# Arducard.net
KiCad netlist of a schematic drawn in EAGLE
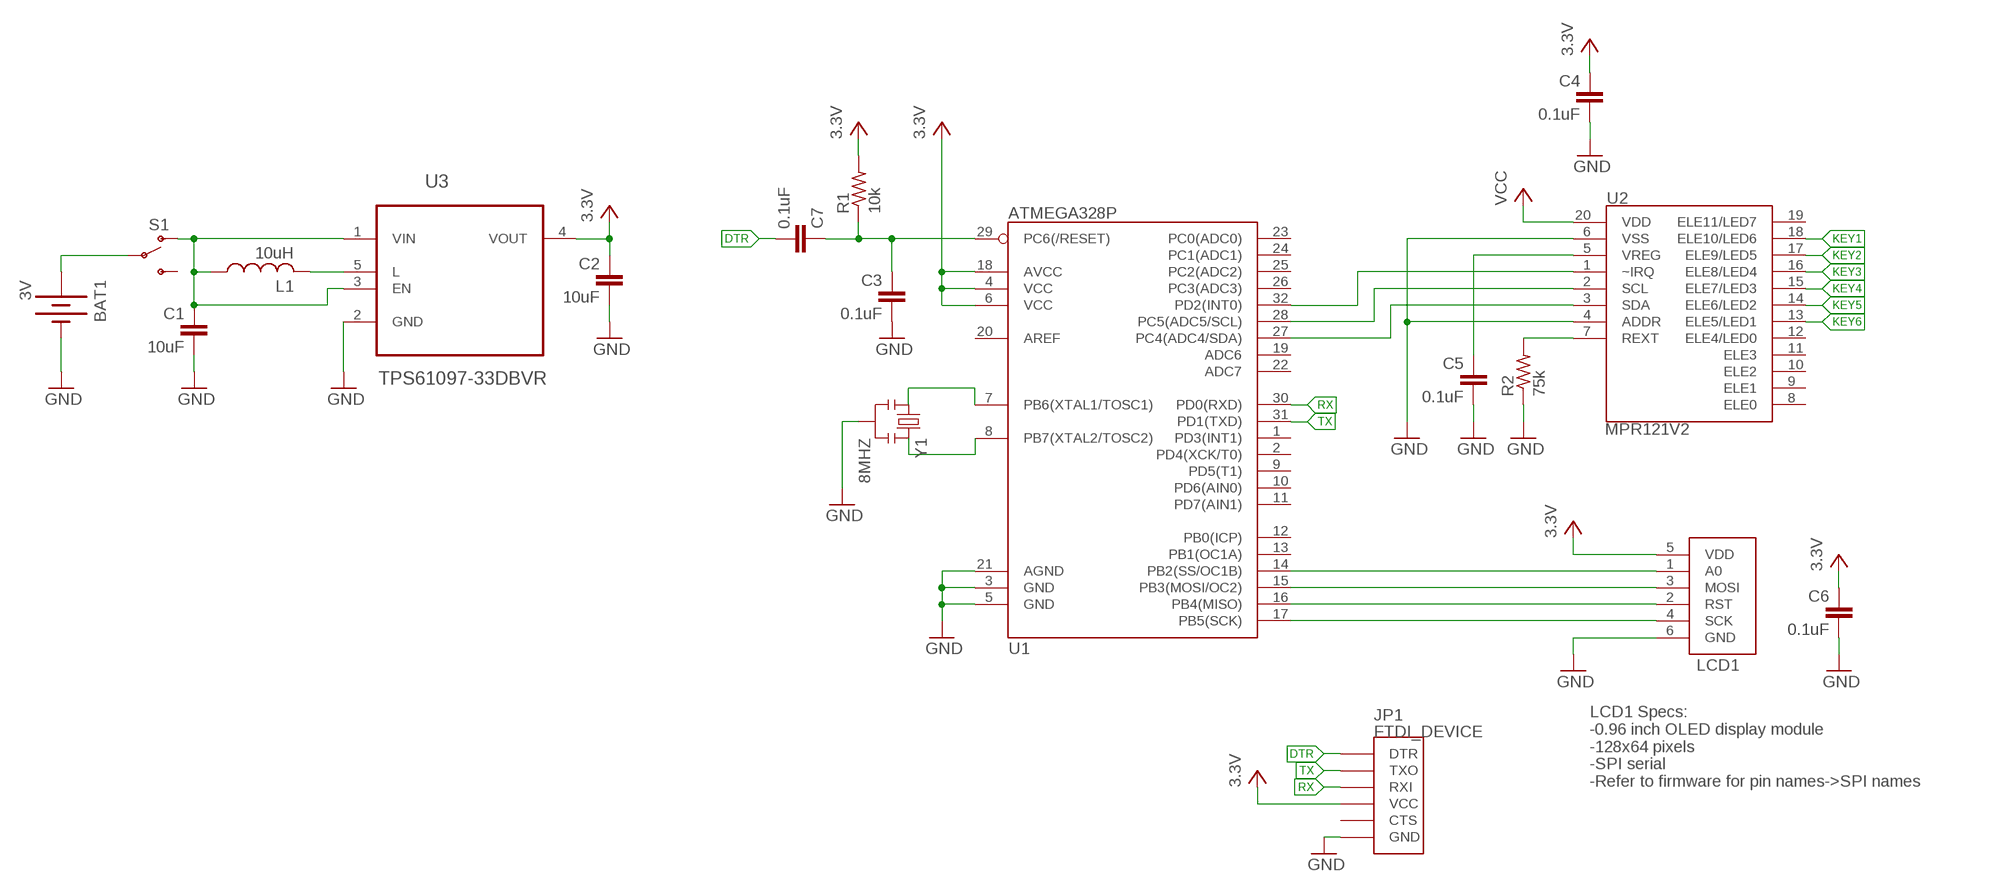
[diagram p0: schematic, sheet 1]

(export (version "E")
  (design (tool "Eeschema 10.0.6"))
  (components
    (comp (ref "BAT1")
      (value "3V")
      (footprint "eagle-import:BATTCON_20MM_4LEGS")
      (libsource (lib "eagle-import") (part "BATTERY20MM_4LEGS"))
    )
    (comp (ref "C1")
      (value "10uF")
      (footprint "eagle-import:C0603K")
      (libsource (lib "eagle-import") (part "C-EUC0603K"))
    )
    (comp (ref "C2")
      (value "10uF")
      (footprint "eagle-import:C0603K")
      (libsource (lib "eagle-import") (part "C-EUC0603K"))
    )
    (comp (ref "C3")
      (value "0.1uF")
      (footprint "eagle-import:C0603K")
      (libsource (lib "eagle-import") (part "C-EUC0603K"))
    )
    (comp (ref "C4")
      (value "0.1uF")
      (footprint "eagle-import:C0603K")
      (libsource (lib "eagle-import") (part "C-EUC0603K"))
    )
    (comp (ref "C5")
      (value "0.1uF")
      (footprint "eagle-import:C0603K")
      (libsource (lib "eagle-import") (part "C-EUC0603K"))
    )
    (comp (ref "C6")
      (value "0.1uF")
      (footprint "eagle-import:C0603K")
      (libsource (lib "eagle-import") (part "C-EUC0603K"))
    )
    (comp (ref "C7")
      (value "0.1uF")
      (footprint "eagle-import:C0603K")
      (libsource (lib "eagle-import") (part "C-EUC0603K"))
    )
    (comp (ref "JP1")
      (value "FTDI_DEVICE")
      (footprint "eagle-import:FTDI_DEVICE_SIDE")
      (libsource (lib "eagle-import") (part "FTDI_DEVICE"))
    )
    (comp (ref "L1")
      (value "10uH")
      (footprint "eagle-import:L2012C")
      (fields (field (name "MPN") "CKS21254R7M-T"))
      (libsource (lib "eagle-import") (part "L-USL2012C"))
    )
    (comp (ref "LCD1")
      (value "LCD")
      (footprint "eagle-import:LCD")
      (libsource (lib "eagle-import") (part "LCD"))
    )
    (comp (ref "R1")
      (value "10k")
      (footprint "eagle-import:R0603")
      (libsource (lib "eagle-import") (part "R-US_R0603"))
    )
    (comp (ref "R2")
      (value "75k")
      (footprint "eagle-import:R0603")
      (libsource (lib "eagle-import") (part "R-US_R0603"))
    )
    (comp (ref "S1")
      (value "SWITCH-SPDTSMD2")
      (footprint "eagle-import:SWITCH-SPDT-SMD")
      (libsource (lib "eagle-import") (part "SWITCH-SPDTSMD2"))
    )
    (comp (ref "U1")
      (value "ATMEGA328P")
      (footprint "eagle-import:TQFP32-08")
      (libsource (lib "eagle-import") (part "ATMEGA328_SMT"))
    )
    (comp (ref "U2")
      (value "MPR121V2")
      (footprint "eagle-import:QFN-20-0.4MM-V2")
      (libsource (lib "eagle-import") (part "MPR121V2"))
    )
    (comp (ref "U3")
      (value "TPS61097-33DBVR")
      (footprint "eagle-import:SOT95P280X145-5N")
      (libsource (lib "eagle-import") (part "TPS61097-33DBVR"))
    )
    (comp (ref "Y1")
      (value "8MHZ")
      (footprint "eagle-import:RESONATOR-SMD")
      (libsource (lib "eagle-import") (part "RESONATOR16MHZ"))
    )
  )
  (nets
    (net (code "1") (name "3.3V") (class "Default")
      (node (ref "C2") (pin "1") (pinfunction "1_1") (pintype "passive"))
      (node (ref "C4") (pin "1") (pinfunction "1_1") (pintype "passive"))
      (node (ref "C6") (pin "1") (pinfunction "1_1") (pintype "passive"))
      (node (ref "JP1") (pin "P$4") (pinfunction "VCC_P$4") (pintype "bidirectional"))
      (node (ref "LCD1") (pin "5") (pinfunction "VDD_5") (pintype "bidirectional"))
      (node (ref "R1") (pin "2") (pinfunction "2_2") (pintype "passive"))
      (node (ref "U1") (pin "18") (pinfunction "AVCC_18") (pintype "bidirectional"))
      (node (ref "U1") (pin "4") (pinfunction "VCC_4") (pintype "bidirectional"))
      (node (ref "U1") (pin "6") (pinfunction "VCC_6") (pintype "bidirectional"))
      (node (ref "U2") (pin "20") (pinfunction "VDD_20") (pintype "bidirectional"))
      (node (ref "U3") (pin "4") (pinfunction "VOUT_4") (pintype "output"))
    )
    (net (code "2") (name "DTR") (class "Default")
      (node (ref "C7") (pin "2") (pinfunction "2_2") (pintype "passive"))
      (node (ref "JP1") (pin "P$1") (pinfunction "DTR_P$1") (pintype "bidirectional"))
    )
    (net (code "3") (name "GND") (class "Default")
      (node (ref "BAT1") (pin "2") (pinfunction "-_2") (pintype "power_in"))
      (node (ref "C1") (pin "2") (pinfunction "2_2") (pintype "passive"))
      (node (ref "C2") (pin "2") (pinfunction "2_2") (pintype "passive"))
      (node (ref "C3") (pin "2") (pinfunction "2_2") (pintype "passive"))
      (node (ref "C4") (pin "2") (pinfunction "2_2") (pintype "passive"))
      (node (ref "C5") (pin "2") (pinfunction "2_2") (pintype "passive"))
      (node (ref "C6") (pin "2") (pinfunction "2_2") (pintype "passive"))
      (node (ref "JP1") (pin "P$6") (pinfunction "GND_P$6") (pintype "bidirectional"))
      (node (ref "LCD1") (pin "6") (pinfunction "GND_6") (pintype "bidirectional"))
      (node (ref "R2") (pin "1") (pinfunction "1_1") (pintype "passive"))
      (node (ref "U1") (pin "21") (pinfunction "AGND_21") (pintype "bidirectional"))
      (node (ref "U1") (pin "3") (pinfunction "GND_3") (pintype "bidirectional"))
      (node (ref "U1") (pin "5") (pinfunction "GND_5") (pintype "bidirectional"))
      (node (ref "U2") (pin "4") (pinfunction "ADDR_4") (pintype "bidirectional"))
      (node (ref "U2") (pin "6") (pinfunction "VSS_6") (pintype "bidirectional"))
      (node (ref "U3") (pin "2") (pinfunction "GND_2") (pintype "passive"))
      (node (ref "Y1") (pin "2") (pinfunction "2_2") (pintype "passive"))
    )
    (net (code "4") (name "KEY1") (class "Default")
      (node (ref "U2") (pin "18") (pinfunction "ELE10/LED6_18") (pintype "bidirectional"))
    )
    (net (code "5") (name "KEY2") (class "Default")
      (node (ref "U2") (pin "17") (pinfunction "ELE9/LED5_17") (pintype "bidirectional"))
    )
    (net (code "6") (name "KEY3") (class "Default")
      (node (ref "U2") (pin "16") (pinfunction "ELE8/LED4_16") (pintype "bidirectional"))
    )
    (net (code "7") (name "KEY4") (class "Default")
      (node (ref "U2") (pin "15") (pinfunction "ELE7/LED3_15") (pintype "bidirectional"))
    )
    (net (code "8") (name "KEY5") (class "Default")
      (node (ref "U2") (pin "14") (pinfunction "ELE6/LED2_14") (pintype "bidirectional"))
    )
    (net (code "9") (name "KEY6") (class "Default")
      (node (ref "U2") (pin "13") (pinfunction "ELE5/LED1_13") (pintype "bidirectional"))
    )
    (net (code "10") (name "Net-(BAT1-+)") (class "Default")
      (node (ref "BAT1") (pin "P$2") (pinfunction "+_P$2") (pintype "power_in"))
      (node (ref "S1") (pin "2") (pinfunction "P_2") (pintype "passive"))
    )
    (net (code "11") (name "Net-(LCD1-A0)") (class "Default")
      (node (ref "LCD1") (pin "1") (pinfunction "A0_1") (pintype "bidirectional"))
      (node (ref "U1") (pin "14") (pinfunction "PB2(SS/OC1B)_14") (pintype "bidirectional"))
    )
    (net (code "12") (name "Net-(LCD1-MOSI)") (class "Default")
      (node (ref "LCD1") (pin "3") (pinfunction "MOSI_3") (pintype "bidirectional"))
      (node (ref "U1") (pin "15") (pinfunction "PB3(MOSI/OC2)_15") (pintype "bidirectional"))
    )
    (net (code "13") (name "Net-(LCD1-RST)") (class "Default")
      (node (ref "LCD1") (pin "2") (pinfunction "RST_2") (pintype "bidirectional"))
      (node (ref "U1") (pin "16") (pinfunction "PB4(MISO)_16") (pintype "bidirectional"))
    )
    (net (code "14") (name "Net-(LCD1-SCK)") (class "Default")
      (node (ref "LCD1") (pin "4") (pinfunction "SCK_4") (pintype "bidirectional"))
      (node (ref "U1") (pin "17") (pinfunction "PB5(SCK)_17") (pintype "bidirectional"))
    )
    (net (code "15") (name "Net-(S1-O)") (class "Default")
      (node (ref "C1") (pin "1") (pinfunction "1_1") (pintype "passive"))
      (node (ref "L1") (pin "1") (pinfunction "1_1") (pintype "passive"))
      (node (ref "S1") (pin "1") (pinfunction "O_1") (pintype "passive"))
      (node (ref "U3") (pin "1") (pinfunction "VIN_1") (pintype "power_in"))
      (node (ref "U3") (pin "3") (pinfunction "EN_3") (pintype "input"))
    )
    (net (code "16") (name "Net-(U1-PB6(XTAL1{slash}TOSC1))") (class "Default")
      (node (ref "U1") (pin "7") (pinfunction "PB6(XTAL1/TOSC1)_7") (pintype "bidirectional"))
      (node (ref "Y1") (pin "1") (pinfunction "1_1") (pintype "passive"))
    )
    (net (code "17") (name "Net-(U1-PB7(XTAL2{slash}TOSC2))") (class "Default")
      (node (ref "U1") (pin "8") (pinfunction "PB7(XTAL2/TOSC2)_8") (pintype "bidirectional"))
      (node (ref "Y1") (pin "3") (pinfunction "3_3") (pintype "passive"))
    )
    (net (code "18") (name "Net-(U1-PC4(ADC4{slash}SDA))") (class "Default")
      (node (ref "U1") (pin "27") (pinfunction "PC4(ADC4/SDA)_27") (pintype "bidirectional"))
      (node (ref "U2") (pin "3") (pinfunction "SDA_3") (pintype "bidirectional"))
    )
    (net (code "19") (name "Net-(U1-PC5(ADC5{slash}SCL))") (class "Default")
      (node (ref "U1") (pin "28") (pinfunction "PC5(ADC5/SCL)_28") (pintype "bidirectional"))
      (node (ref "U2") (pin "2") (pinfunction "SCL_2") (pintype "bidirectional"))
    )
    (net (code "20") (name "Net-(U1-PC6({slash}RESET))") (class "Default")
      (node (ref "C3") (pin "1") (pinfunction "1_1") (pintype "passive"))
      (node (ref "C7") (pin "1") (pinfunction "1_1") (pintype "passive"))
      (node (ref "R1") (pin "1") (pinfunction "1_1") (pintype "passive"))
      (node (ref "U1") (pin "29") (pinfunction "PC6(/RESET)_29") (pintype "bidirectional"))
    )
    (net (code "21") (name "Net-(U1-PD2(INT0))") (class "Default")
      (node (ref "U1") (pin "32") (pinfunction "PD2(INT0)_32") (pintype "bidirectional"))
      (node (ref "U2") (pin "1") (pinfunction "~{IRQ}_1") (pintype "bidirectional"))
    )
    (net (code "22") (name "Net-(U2-REXT)") (class "Default")
      (node (ref "R2") (pin "2") (pinfunction "2_2") (pintype "passive"))
      (node (ref "U2") (pin "7") (pinfunction "REXT_7") (pintype "bidirectional"))
    )
    (net (code "23") (name "Net-(U2-VREG)") (class "Default")
      (node (ref "C5") (pin "1") (pinfunction "1_1") (pintype "passive"))
      (node (ref "U2") (pin "5") (pinfunction "VREG_5") (pintype "bidirectional"))
    )
    (net (code "24") (name "Net-(U3-L)") (class "Default")
      (node (ref "L1") (pin "2") (pinfunction "2_2") (pintype "passive"))
      (node (ref "U3") (pin "5") (pinfunction "L_5") (pintype "input"))
    )
    (net (code "25") (name "RX") (class "Default")
      (node (ref "JP1") (pin "P$3") (pinfunction "RXI_P$3") (pintype "bidirectional"))
      (node (ref "U1") (pin "30") (pinfunction "PD0(RXD)_30") (pintype "bidirectional"))
    )
    (net (code "26") (name "TX") (class "Default")
      (node (ref "JP1") (pin "P$2") (pinfunction "TXO_P$2") (pintype "bidirectional"))
      (node (ref "U1") (pin "31") (pinfunction "PD1(TXD)_31") (pintype "bidirectional"))
    )
    (net (code "27") (name "unconnected-(JP1-CTS-PadP$5)") (class "Default")
      (node (ref "JP1") (pin "P$5") (pinfunction "CTS_P$5") (pintype "bidirectional"))
    )
    (net (code "28") (name "unconnected-(S1-S-Pad3)") (class "Default")
      (node (ref "S1") (pin "3") (pinfunction "S_3") (pintype "passive"))
    )
    (net (code "29") (name "unconnected-(U1-ADC6-Pad19)") (class "Default")
      (node (ref "U1") (pin "19") (pinfunction "ADC6_19") (pintype "bidirectional"))
    )
    (net (code "30") (name "unconnected-(U1-ADC7-Pad22)") (class "Default")
      (node (ref "U1") (pin "22") (pinfunction "ADC7_22") (pintype "bidirectional"))
    )
    (net (code "31") (name "unconnected-(U1-AREF-Pad20)") (class "Default")
      (node (ref "U1") (pin "20") (pinfunction "AREF_20") (pintype "bidirectional"))
    )
    (net (code "32") (name "unconnected-(U1-PB0(ICP)-Pad12)") (class "Default")
      (node (ref "U1") (pin "12") (pinfunction "PB0(ICP)_12") (pintype "bidirectional"))
    )
    (net (code "33") (name "unconnected-(U1-PB1(OC1A)-Pad13)") (class "Default")
      (node (ref "U1") (pin "13") (pinfunction "PB1(OC1A)_13") (pintype "bidirectional"))
    )
    (net (code "34") (name "unconnected-(U1-PC0(ADC0)-Pad23)") (class "Default")
      (node (ref "U1") (pin "23") (pinfunction "PC0(ADC0)_23") (pintype "bidirectional"))
    )
    (net (code "35") (name "unconnected-(U1-PC1(ADC1)-Pad24)") (class "Default")
      (node (ref "U1") (pin "24") (pinfunction "PC1(ADC1)_24") (pintype "bidirectional"))
    )
    (net (code "36") (name "unconnected-(U1-PC2(ADC2)-Pad25)") (class "Default")
      (node (ref "U1") (pin "25") (pinfunction "PC2(ADC2)_25") (pintype "bidirectional"))
    )
    (net (code "37") (name "unconnected-(U1-PC3(ADC3)-Pad26)") (class "Default")
      (node (ref "U1") (pin "26") (pinfunction "PC3(ADC3)_26") (pintype "bidirectional"))
    )
    (net (code "38") (name "unconnected-(U1-PD3(INT1)-Pad1)") (class "Default")
      (node (ref "U1") (pin "1") (pinfunction "PD3(INT1)_1") (pintype "bidirectional"))
    )
    (net (code "39") (name "unconnected-(U1-PD4(XCK{slash}T0)-Pad2)") (class "Default")
      (node (ref "U1") (pin "2") (pinfunction "PD4(XCK/T0)_2") (pintype "bidirectional"))
    )
    (net (code "40") (name "unconnected-(U1-PD5(T1)-Pad9)") (class "Default")
      (node (ref "U1") (pin "9") (pinfunction "PD5(T1)_9") (pintype "bidirectional"))
    )
    (net (code "41") (name "unconnected-(U1-PD6(AIN0)-Pad10)") (class "Default")
      (node (ref "U1") (pin "10") (pinfunction "PD6(AIN0)_10") (pintype "bidirectional"))
    )
    (net (code "42") (name "unconnected-(U1-PD7(AIN1)-Pad11)") (class "Default")
      (node (ref "U1") (pin "11") (pinfunction "PD7(AIN1)_11") (pintype "bidirectional"))
    )
    (net (code "43") (name "unconnected-(U2-ELE0-Pad8)") (class "Default")
      (node (ref "U2") (pin "8") (pinfunction "ELE0_8") (pintype "bidirectional"))
    )
    (net (code "44") (name "unconnected-(U2-ELE1-Pad9)") (class "Default")
      (node (ref "U2") (pin "9") (pinfunction "ELE1_9") (pintype "bidirectional"))
    )
    (net (code "45") (name "unconnected-(U2-ELE2-Pad10)") (class "Default")
      (node (ref "U2") (pin "10") (pinfunction "ELE2_10") (pintype "bidirectional"))
    )
    (net (code "46") (name "unconnected-(U2-ELE3-Pad11)") (class "Default")
      (node (ref "U2") (pin "11") (pinfunction "ELE3_11") (pintype "bidirectional"))
    )
    (net (code "47") (name "unconnected-(U2-ELE4{slash}LED0-Pad12)") (class "Default")
      (node (ref "U2") (pin "12") (pinfunction "ELE4/LED0_12") (pintype "bidirectional"))
    )
    (net (code "48") (name "unconnected-(U2-ELE11{slash}LED7-Pad19)") (class "Default")
      (node (ref "U2") (pin "19") (pinfunction "ELE11/LED7_19") (pintype "bidirectional"))
    )
  )
)
